# USB-HUB-MUX.net
KiCad netlist of a schematic drawn in Altium Designer
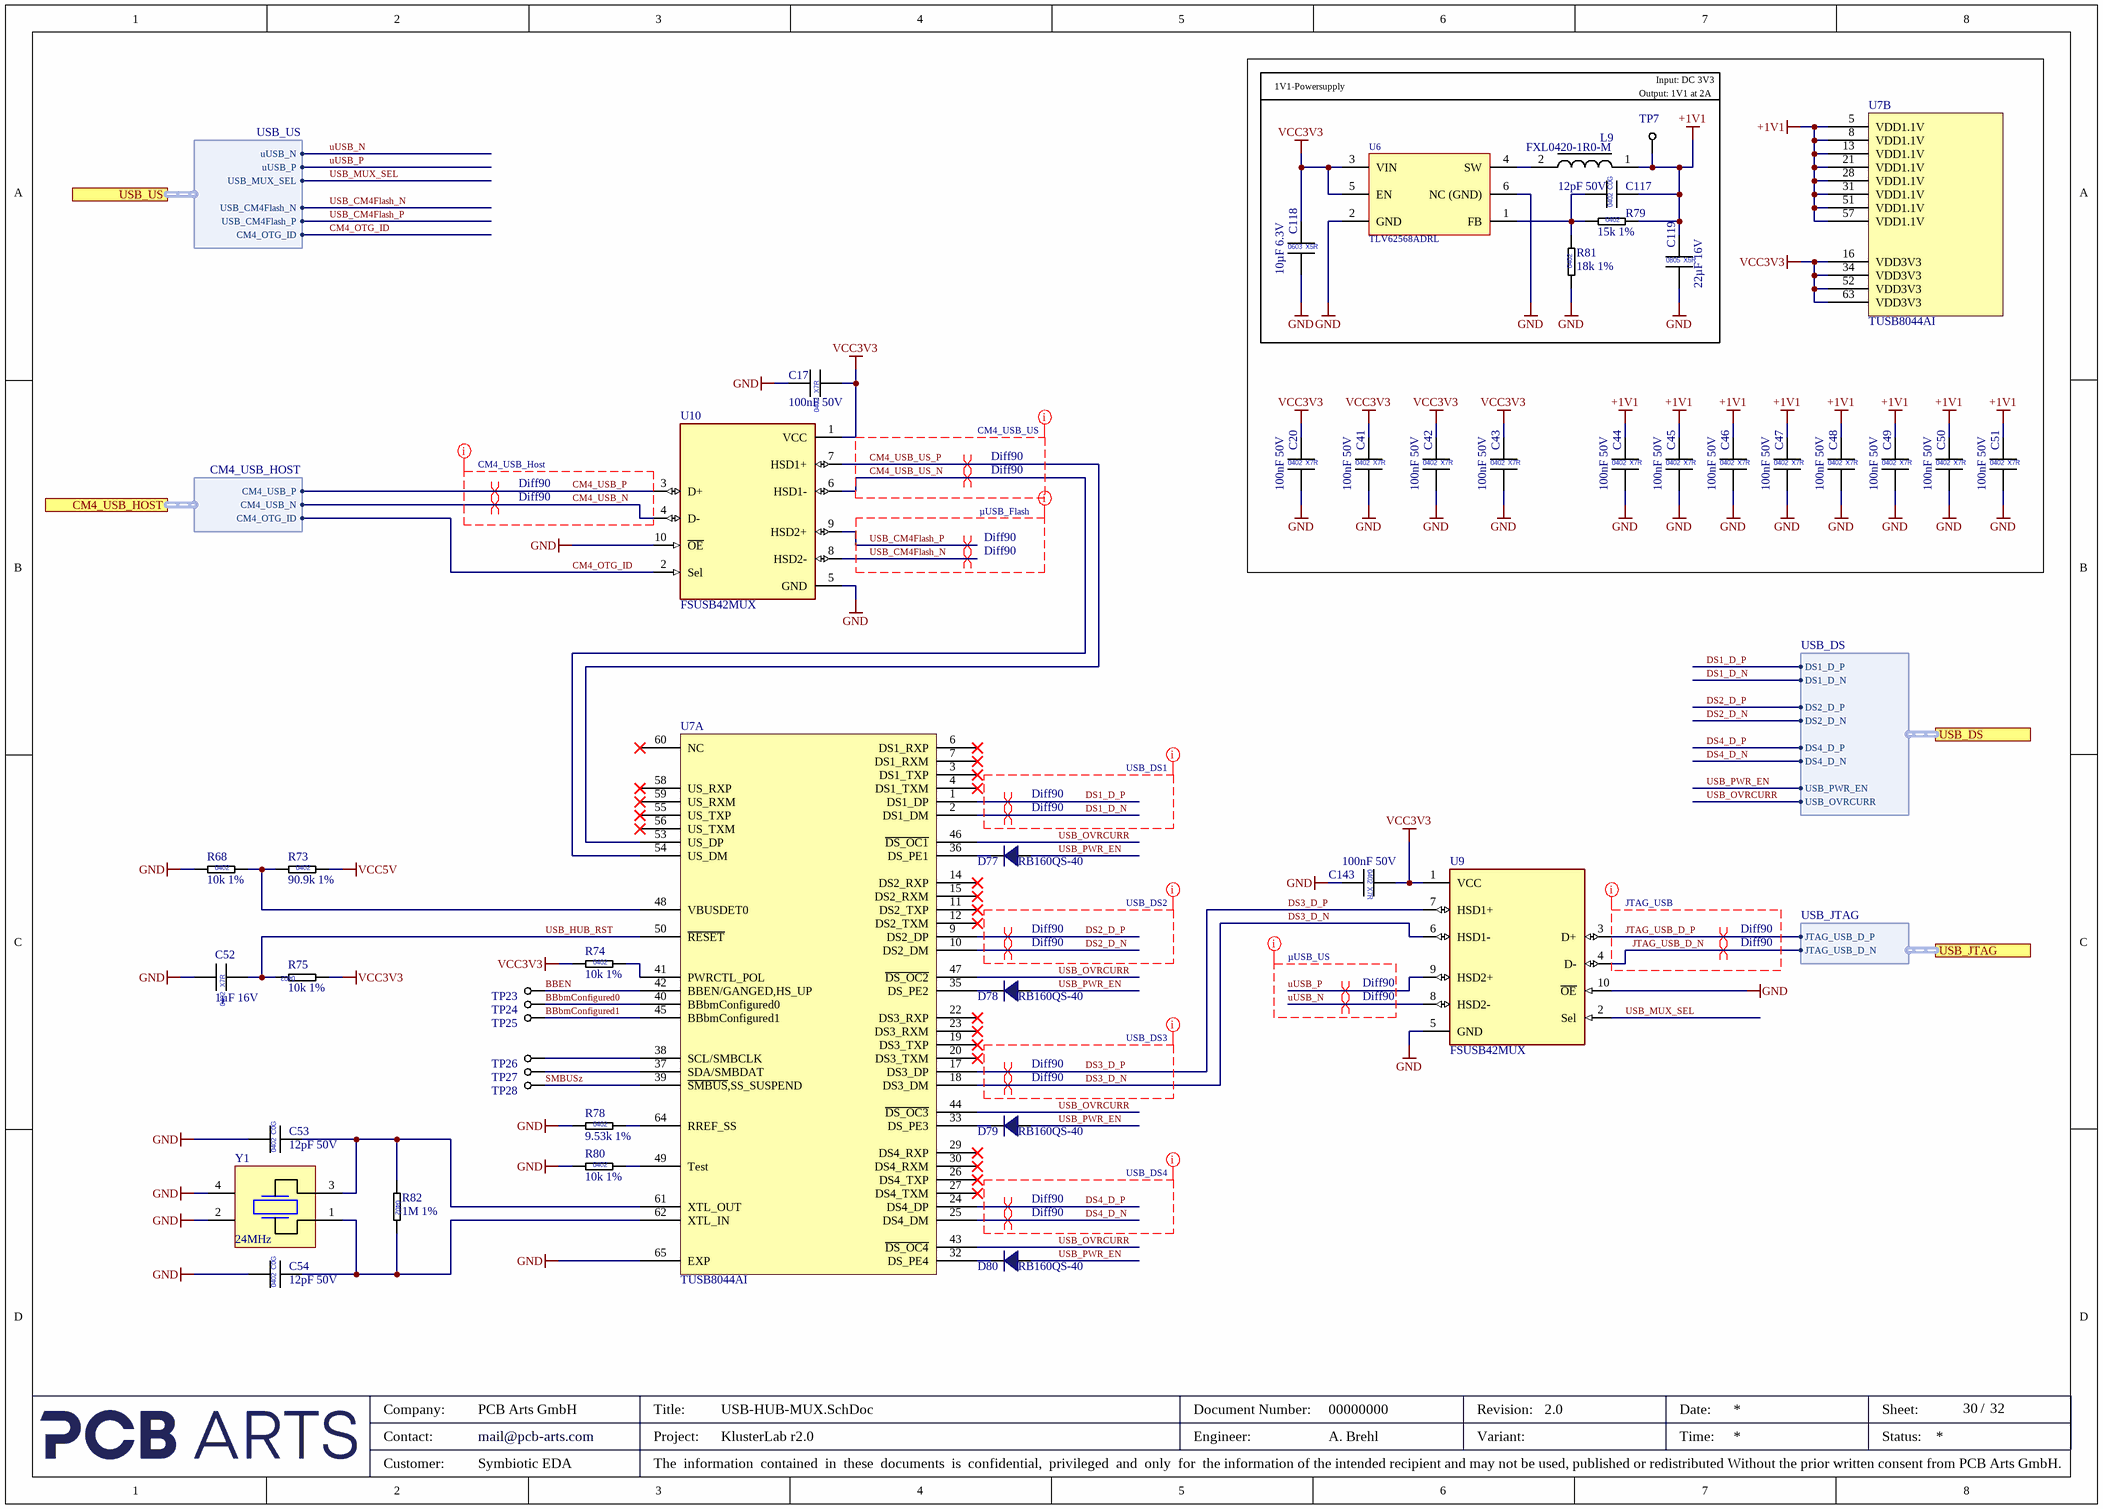
[diagram p0: USB-HUB-MUX.SchDoc]

(export (version "E")
  (design (tool "Eeschema 10.0.6"))
  (components
    (comp (ref "C17")
      (value "100nF 50V")
      (footprint "Cap:CAP_0402_L")
      (description "Multilayer Ceramic Capacitors MLCC - SMD/SMT 0402 50VDC")
      (libsource (lib "Cap") (part "CAP_0402_100nF_50V"))
    )
    (comp (ref "C20")
      (value "100nF 50V")
      (footprint "Cap:CAP_0402_L")
      (description "Multilayer Ceramic Capacitors MLCC - SMD/SMT 0402 50VDC")
      (libsource (lib "Cap") (part "CAP_0402_100nF_50V"))
    )
    (comp (ref "C41")
      (value "100nF 50V")
      (footprint "Cap:CAP_0402_L")
      (description "Multilayer Ceramic Capacitors MLCC - SMD/SMT 0402 50VDC")
      (libsource (lib "Cap") (part "CAP_0402_100nF_50V"))
    )
    (comp (ref "C42")
      (value "100nF 50V")
      (footprint "Cap:CAP_0402_L")
      (description "Multilayer Ceramic Capacitors MLCC - SMD/SMT 0402 50VDC")
      (libsource (lib "Cap") (part "CAP_0402_100nF_50V"))
    )
    (comp (ref "C43")
      (value "100nF 50V")
      (footprint "Cap:CAP_0402_L")
      (description "Multilayer Ceramic Capacitors MLCC - SMD/SMT 0402 50VDC")
      (libsource (lib "Cap") (part "CAP_0402_100nF_50V"))
    )
    (comp (ref "C44")
      (value "100nF 50V")
      (footprint "Cap:CAP_0402_L")
      (description "Multilayer Ceramic Capacitors MLCC - SMD/SMT 0402 50VDC")
      (libsource (lib "Cap") (part "CAP_0402_100nF_50V"))
    )
    (comp (ref "C45")
      (value "100nF 50V")
      (footprint "Cap:CAP_0402_L")
      (description "Multilayer Ceramic Capacitors MLCC - SMD/SMT 0402 50VDC")
      (libsource (lib "Cap") (part "CAP_0402_100nF_50V"))
    )
    (comp (ref "C46")
      (value "100nF 50V")
      (footprint "Cap:CAP_0402_L")
      (description "Multilayer Ceramic Capacitors MLCC - SMD/SMT 0402 50VDC")
      (libsource (lib "Cap") (part "CAP_0402_100nF_50V"))
    )
    (comp (ref "C47")
      (value "100nF 50V")
      (footprint "Cap:CAP_0402_L")
      (description "Multilayer Ceramic Capacitors MLCC - SMD/SMT 0402 50VDC")
      (libsource (lib "Cap") (part "CAP_0402_100nF_50V"))
    )
    (comp (ref "C48")
      (value "100nF 50V")
      (footprint "Cap:CAP_0402_L")
      (description "Multilayer Ceramic Capacitors MLCC - SMD/SMT 0402 50VDC")
      (libsource (lib "Cap") (part "CAP_0402_100nF_50V"))
    )
    (comp (ref "C49")
      (value "100nF 50V")
      (footprint "Cap:CAP_0402_L")
      (description "Multilayer Ceramic Capacitors MLCC - SMD/SMT 0402 50VDC")
      (libsource (lib "Cap") (part "CAP_0402_100nF_50V"))
    )
    (comp (ref "C50")
      (value "100nF 50V")
      (footprint "Cap:CAP_0402_L")
      (description "Multilayer Ceramic Capacitors MLCC - SMD/SMT 0402 50VDC")
      (libsource (lib "Cap") (part "CAP_0402_100nF_50V"))
    )
    (comp (ref "C51")
      (value "100nF 50V")
      (footprint "Cap:CAP_0402_L")
      (description "Multilayer Ceramic Capacitors MLCC - SMD/SMT 0402 50VDC")
      (libsource (lib "Cap") (part "CAP_0402_100nF_50V"))
    )
    (comp (ref "C52")
      (value "1µF 16V")
      (footprint "CAP_0402_L")
      (description "Multilayer Ceramic Capacitors MLCC - SMD/SMT 0402 16VDC")
      (libsource (lib "MIKO 202007") (part "CAP_0402_1µF_16V"))
    )
    (comp (ref "C53")
      (value "12pF 50V")
      (footprint "Cap:CAP_0402_L")
      (description "Multilayer Ceramic Capacitors MLCC - SMD/SMT 0402 50VDC")
      (libsource (lib "Cap") (part "CAP_0402_12pF_50V"))
    )
    (comp (ref "C54")
      (value "12pF 50V")
      (footprint "Cap:CAP_0402_L")
      (description "Multilayer Ceramic Capacitors MLCC - SMD/SMT 0402 50VDC")
      (libsource (lib "Cap") (part "CAP_0402_12pF_50V"))
    )
    (comp (ref "C117")
      (value "12pF 50V")
      (footprint "Cap:CAP_0402_L")
      (description "Multilayer Ceramic Capacitors MLCC - SMD/SMT 0402 50VDC")
      (libsource (lib "Cap") (part "CAP_0402_12pF_50V"))
    )
    (comp (ref "C118")
      (value "10µF 6.3V")
      (footprint "Cap:CAP_0603_L")
      (description "Multilayer Ceramic Capacitors MLCC - SMD/SMT 0603 6.3VDC")
      (libsource (lib "Cap") (part "CAP_0603_10µF_6.3V"))
    )
    (comp (ref "C119")
      (value "22µF 16V")
      (footprint "Cap:CAP_0805")
      (description "Multilayer Ceramic Capacitors MLCC - SMD/SMT 0805 16VDC")
      (libsource (lib "Cap") (part "CAP_0805_22µF_16V"))
    )
    (comp (ref "C143")
      (value "100nF 50V")
      (footprint "Cap:CAP_0402_L")
      (description "Multilayer Ceramic Capacitors MLCC - SMD/SMT 0402 50VDC")
      (libsource (lib "Cap") (part "CAP_0402_100nF_50V"))
    )
    (comp (ref "D77")
      (value "RB160QS-40")
      (footprint "Active:SOD-882")
      (description "Schottky Dioden & Gleichrichter 40V SCHOTTKY DIODES & RECTIFIERS")
      (libsource (lib "Active") (part "RB160QS-40_Schottky Dioden & Gleichrichter 40V"))
    )
    (comp (ref "D78")
      (value "RB160QS-40")
      (footprint "Active:SOD-882")
      (description "Schottky Dioden & Gleichrichter 40V SCHOTTKY DIODES & RECTIFIERS")
      (libsource (lib "Active") (part "RB160QS-40_Schottky Dioden & Gleichrichter 40V"))
    )
    (comp (ref "D79")
      (value "RB160QS-40")
      (footprint "Active:SOD-882")
      (description "Schottky Dioden & Gleichrichter 40V SCHOTTKY DIODES & RECTIFIERS")
      (libsource (lib "Active") (part "RB160QS-40_Schottky Dioden & Gleichrichter 40V"))
    )
    (comp (ref "D80")
      (value "RB160QS-40")
      (footprint "Active:SOD-882")
      (description "Schottky Dioden & Gleichrichter 40V SCHOTTKY DIODES & RECTIFIERS")
      (libsource (lib "Active") (part "RB160QS-40_Schottky Dioden & Gleichrichter 40V"))
    )
    (comp (ref "L9")
      (value "FXL0420-1R0-M")
      (footprint "Indc:FXL0420-1R0-M")
      (description "1uH ±20% 6A 27mΩ SMD,4.4x4.5x1.8mm Power Inductor")
      (libsource (lib "Indc") (part "1uH 6A 27mΩ  FXL0420-1R0-M"))
    )
    (comp (ref "R68")
      (value "10k 1%")
      (footprint "Res:RES_0402_L")
      (description "Thick Film Resistors - SMD 10kOhm 1%")
      (libsource (lib "Res") (part "RES_0402_10k_1%"))
    )
    (comp (ref "R73")
      (value "90.9k 1%")
      (footprint "Res:RES_0402_L")
      (description "Thick Film Resistors - SMD 90.9k 1%")
      (libsource (lib "Res") (part "RES_0402_90.9k_1%"))
    )
    (comp (ref "R74")
      (value "10k 1%")
      (footprint "Res:RES_0402_L")
      (description "Thick Film Resistors - SMD 10kOhm 1%")
      (libsource (lib "Res") (part "RES_0402_10k_1%"))
    )
    (comp (ref "R75")
      (value "10k 1%")
      (footprint "Res:RES_0402_L")
      (description "Thick Film Resistors - SMD 10kOhm 1%")
      (libsource (lib "Res") (part "RES_0402_10k_1%"))
    )
    (comp (ref "R78")
      (value "9.53k 1%")
      (footprint "Res:RES_0402_L")
      (description "Thick Film Resistors - SMD 9.53kOhm 1%")
      (libsource (lib "Res") (part "RES_0402_9.53k_1%"))
    )
    (comp (ref "R79")
      (value "15k 1%")
      (footprint "Res:RES_0402_L")
      (description "Thick Film Resistors - SMD 15kOhm 1%")
      (libsource (lib "Res") (part "RES_0402_15k_1%"))
    )
    (comp (ref "R80")
      (value "10k 1%")
      (footprint "Res:RES_0402_L")
      (description "Thick Film Resistors - SMD 10kOhm 1%")
      (libsource (lib "Res") (part "RES_0402_10k_1%"))
    )
    (comp (ref "R81")
      (value "18k 1%")
      (footprint "Res:RES_0402_L")
      (description "Thick Film Resistors - SMD 18kOhm 1%")
      (libsource (lib "Res") (part "RES_0402_18k_1%"))
    )
    (comp (ref "R82")
      (value "1M 1%")
      (footprint "Res:RES_0402_L")
      (description "Thick Film Resistors - SMD 1MOhm 1%")
      (libsource (lib "Res") (part "RES_0402_1M_1%"))
    )
    (comp (ref "TP7")
      (value "Testpoint")
      (footprint "Electro_mech:Testpoint 0.8mm")
      (description "Testpoint 0.8mm")
      (libsource (lib "Electro_Mech") (part "Testpoint 0.8mm"))
    )
    (comp (ref "TP23")
      (value "Testpoint")
      (footprint "Electro_mech:Testpoint 0.8mm")
      (description "Testpoint 0.8mm")
      (libsource (lib "Electro_Mech") (part "Testpoint 0.8mm"))
    )
    (comp (ref "TP24")
      (value "Testpoint")
      (footprint "Electro_mech:Testpoint 0.8mm")
      (description "Testpoint 0.8mm")
      (libsource (lib "Electro_Mech") (part "Testpoint 0.8mm"))
    )
    (comp (ref "TP25")
      (value "Testpoint")
      (footprint "Electro_mech:Testpoint 0.8mm")
      (description "Testpoint 0.8mm")
      (libsource (lib "Electro_Mech") (part "Testpoint 0.8mm"))
    )
    (comp (ref "TP26")
      (value "Testpoint")
      (footprint "Electro_mech:Testpoint 0.8mm")
      (description "Testpoint 0.8mm")
      (libsource (lib "Electro_Mech") (part "Testpoint 0.8mm"))
    )
    (comp (ref "TP27")
      (value "Testpoint")
      (footprint "Electro_mech:Testpoint 0.8mm")
      (description "Testpoint 0.8mm")
      (libsource (lib "Electro_Mech") (part "Testpoint 0.8mm"))
    )
    (comp (ref "TP28")
      (value "Testpoint")
      (footprint "Electro_mech:Testpoint 0.8mm")
      (description "Testpoint 0.8mm")
      (libsource (lib "Electro_Mech") (part "Testpoint 0.8mm"))
    )
    (comp (ref "U6")
      (value "TLV62568ADRL")
      (footprint "Power:SON50P150X80-6N")
      (description "Step Down Converter with Forced PWM in SOT563 Package")
      (libsource (lib "Power") (part "TLV62568ADRL_Step Down Converter 1A; 2A"))
    )
    (comp (ref "U7")
      (value "TUSB8044AI")
      (footprint "Digital:QFN50P900X900X90_HS-65N")
      (description "USB Hub IC, USB 3.2, 5Gbps, 4 Ports, industrial Temperature")
      (libsource (lib "Digital") (part "TUSB8044AI_USB Hub IC, USB 3.2, 5Gbps, 4 Ports, industrial Temperature"))
    )
    (comp (ref "U9")
      (value "FSUSB42MUX")
      (footprint "digital:SOP50P300X300X110-10N")
      (description "IC USB SWITCH DPDT")
      (libsource (lib "Digital") (part "FSUSB42MUX_IC USB SWITCH DPDT"))
    )
    (comp (ref "U10")
      (value "FSUSB42MUX")
      (footprint "digital:SOP50P300X300X110-10N")
      (description "IC USB SWITCH DPDT")
      (libsource (lib "") (part "FSUSB42MUX_IC USB SWITCH DPDT_1"))
    )
    (comp (ref "Y1")
      (value "ECS-240-10-36B2-CTN-TR")
      (footprint "Timer:ECX-2236B")
      (description "2.5 x 2.0 x 0.55 mm SMD Crystal")
      (fields (field (name "FREQUENCY") "24MHz"))
      (libsource (lib "Timer") (part "Quarz 24MHz ESR 50R10pF"))
    )
  )
  (nets
    (net (code "5") (name "+1V1") (class "Default")
      (node (ref "C117") (pin "2") (pinfunction "2_2") (pintype "passive"))
      (node (ref "C119") (pin "1") (pinfunction "1_1") (pintype "passive"))
      (node (ref "C44") (pin "1") (pinfunction "1_1") (pintype "passive"))
      (node (ref "C45") (pin "1") (pinfunction "1_1") (pintype "passive"))
      (node (ref "C46") (pin "1") (pinfunction "1_1") (pintype "passive"))
      (node (ref "C47") (pin "1") (pinfunction "1_1") (pintype "passive"))
      (node (ref "C48") (pin "1") (pinfunction "1_1") (pintype "passive"))
      (node (ref "C49") (pin "1") (pinfunction "1_1") (pintype "passive"))
      (node (ref "C50") (pin "1") (pinfunction "1_1") (pintype "passive"))
      (node (ref "C51") (pin "1") (pinfunction "1_1") (pintype "passive"))
      (node (ref "L9") (pin "1") (pinfunction "1_1") (pintype "passive"))
      (node (ref "R79") (pin "2") (pinfunction "2_2") (pintype "passive"))
      (node (ref "TP7") (pin "1") (pinfunction "GND_1") (pintype "passive"))
      (node (ref "U7") (pin "13") (pinfunction "VDD1.1V_13") (pintype "passive"))
      (node (ref "U7") (pin "21") (pinfunction "VDD1.1V_21") (pintype "passive"))
      (node (ref "U7") (pin "28") (pinfunction "VDD1.1V_28") (pintype "passive"))
      (node (ref "U7") (pin "31") (pinfunction "VDD1.1V_31") (pintype "passive"))
      (node (ref "U7") (pin "5") (pinfunction "VDD1.1V_5") (pintype "passive"))
      (node (ref "U7") (pin "51") (pinfunction "VDD1.1V_51") (pintype "passive"))
      (node (ref "U7") (pin "57") (pinfunction "VDD1.1V_57") (pintype "passive"))
      (node (ref "U7") (pin "8") (pinfunction "VDD1.1V_8") (pintype "passive"))
    )
    (net (code "6") (name "/BBEN") (class "Default")
      (node (ref "TP23") (pin "1") (pinfunction "GND_1") (pintype "passive"))
      (node (ref "U7") (pin "42") (pinfunction "BBEN/GANGED,HS_UP_42") (pintype "passive"))
    )
    (net (code "7") (name "/BBbmConfigured0") (class "Default")
      (node (ref "TP24") (pin "1") (pinfunction "GND_1") (pintype "passive"))
      (node (ref "U7") (pin "40") (pinfunction "BBbmConfigured0_40") (pintype "passive"))
    )
    (net (code "8") (name "/BBbmConfigured1") (class "Default")
      (node (ref "TP25") (pin "1") (pinfunction "GND_1") (pintype "passive"))
      (node (ref "U7") (pin "45") (pinfunction "BBbmConfigured1_45") (pintype "passive"))
    )
    (net (code "9") (name "/CM4_OTG_ID") (class "Default")
      (node (ref "U10") (pin "2") (pinfunction "Sel_2") (pintype "input"))
    )
    (net (code "10") (name "/CM4_USB_N") (class "Default")
      (node (ref "U10") (pin "4") (pinfunction "D-_4") (pintype "bidirectional"))
    )
    (net (code "11") (name "/CM4_USB_P") (class "Default")
      (node (ref "U10") (pin "3") (pinfunction "D+_3") (pintype "bidirectional"))
    )
    (net (code "12") (name "/CM4_USB_US_N") (class "Default")
      (node (ref "U10") (pin "6") (pinfunction "HSD1-_6") (pintype "bidirectional"))
      (node (ref "U7") (pin "54") (pinfunction "US_DM_54") (pintype "passive"))
    )
    (net (code "13") (name "/CM4_USB_US_P") (class "Default")
      (node (ref "U10") (pin "7") (pinfunction "HSD1+_7") (pintype "bidirectional"))
      (node (ref "U7") (pin "53") (pinfunction "US_DP_53") (pintype "passive"))
    )
    (net (code "14") (name "/DS1_D_N") (class "Default")
      (node (ref "U7") (pin "2") (pinfunction "DS1_DM_2") (pintype "passive"))
    )
    (net (code "15") (name "/DS1_D_P") (class "Default")
      (node (ref "U7") (pin "1") (pinfunction "DS1_DP_1") (pintype "passive"))
    )
    (net (code "16") (name "/DS2_D_N") (class "Default")
      (node (ref "U7") (pin "10") (pinfunction "DS2_DM_10") (pintype "passive"))
    )
    (net (code "17") (name "/DS2_D_P") (class "Default")
      (node (ref "U7") (pin "9") (pinfunction "DS2_DP_9") (pintype "passive"))
    )
    (net (code "18") (name "/DS3_D_N") (class "Default")
      (node (ref "U7") (pin "18") (pinfunction "DS3_DM_18") (pintype "passive"))
      (node (ref "U9") (pin "6") (pinfunction "HSD1-_6") (pintype "bidirectional"))
    )
    (net (code "19") (name "/DS3_D_P") (class "Default")
      (node (ref "U7") (pin "17") (pinfunction "DS3_DP_17") (pintype "passive"))
      (node (ref "U9") (pin "7") (pinfunction "HSD1+_7") (pintype "bidirectional"))
    )
    (net (code "20") (name "/DS4_D_N") (class "Default")
      (node (ref "U7") (pin "25") (pinfunction "DS4_DM_25") (pintype "passive"))
    )
    (net (code "21") (name "/DS4_D_P") (class "Default")
      (node (ref "U7") (pin "24") (pinfunction "DS4_DP_24") (pintype "passive"))
    )
    (net (code "22") (name "/JTAG_USB_D_N") (class "Default")
      (node (ref "U9") (pin "4") (pinfunction "D-_4") (pintype "bidirectional"))
    )
    (net (code "23") (name "/JTAG_USB_D_P") (class "Default")
      (node (ref "U9") (pin "3") (pinfunction "D+_3") (pintype "bidirectional"))
    )
    (net (code "24") (name "/SMBUSz") (class "Default")
      (node (ref "TP28") (pin "1") (pinfunction "GND_1") (pintype "passive"))
      (node (ref "U7") (pin "39") (pinfunction "~{SMBUS},SS_SUSPEND_39") (pintype "passive"))
    )
    (net (code "25") (name "/USB_CM4Flash_N") (class "Default")
      (node (ref "U10") (pin "8") (pinfunction "HSD2-_8") (pintype "bidirectional"))
    )
    (net (code "26") (name "/USB_CM4Flash_P") (class "Default")
      (node (ref "U10") (pin "9") (pinfunction "HSD2+_9") (pintype "bidirectional"))
    )
    (net (code "27") (name "/USB_HUB_RST") (class "Default")
      (node (ref "C52") (pin "1") (pinfunction "1_1") (pintype "passive"))
      (node (ref "R75") (pin "1") (pinfunction "1_1") (pintype "passive"))
      (node (ref "U7") (pin "50") (pinfunction "~{RESET}_50") (pintype "passive"))
    )
    (net (code "28") (name "/USB_MUX_SEL") (class "Default")
      (node (ref "U9") (pin "2") (pinfunction "Sel_2") (pintype "input"))
    )
    (net (code "29") (name "/USB_OVRCURR") (class "Default")
      (node (ref "U7") (pin "43") (pinfunction "~{DS_OC4}_43") (pintype "passive"))
      (node (ref "U7") (pin "44") (pinfunction "~{DS_OC3}_44") (pintype "passive"))
      (node (ref "U7") (pin "46") (pinfunction "~{DS_OC1}_46") (pintype "passive"))
      (node (ref "U7") (pin "47") (pinfunction "~{DS_OC2}_47") (pintype "passive"))
    )
    (net (code "30") (name "/USB_PWR_EN") (class "Default")
      (node (ref "D77") (pin "2") (pinfunction "2_2") (pintype "passive"))
      (node (ref "D78") (pin "2") (pinfunction "2_2") (pintype "passive"))
      (node (ref "D79") (pin "2") (pinfunction "2_2") (pintype "passive"))
      (node (ref "D80") (pin "2") (pinfunction "2_2") (pintype "passive"))
    )
    (net (code "31") (name "/uUSB_N") (class "Default")
      (node (ref "U9") (pin "8") (pinfunction "HSD2-_8") (pintype "bidirectional"))
    )
    (net (code "32") (name "/uUSB_P") (class "Default")
      (node (ref "U9") (pin "9") (pinfunction "HSD2+_9") (pintype "bidirectional"))
    )
    (net (code "37") (name "GND") (class "Default")
      (node (ref "C118") (pin "2") (pinfunction "2_2") (pintype "passive"))
      (node (ref "C119") (pin "2") (pinfunction "2_2") (pintype "passive"))
      (node (ref "C143") (pin "2") (pinfunction "2_2") (pintype "passive"))
      (node (ref "C17") (pin "2") (pinfunction "2_2") (pintype "passive"))
      (node (ref "C20") (pin "2") (pinfunction "2_2") (pintype "passive"))
      (node (ref "C41") (pin "2") (pinfunction "2_2") (pintype "passive"))
      (node (ref "C42") (pin "2") (pinfunction "2_2") (pintype "passive"))
      (node (ref "C43") (pin "2") (pinfunction "2_2") (pintype "passive"))
      (node (ref "C44") (pin "2") (pinfunction "2_2") (pintype "passive"))
      (node (ref "C45") (pin "2") (pinfunction "2_2") (pintype "passive"))
      (node (ref "C46") (pin "2") (pinfunction "2_2") (pintype "passive"))
      (node (ref "C47") (pin "2") (pinfunction "2_2") (pintype "passive"))
      (node (ref "C48") (pin "2") (pinfunction "2_2") (pintype "passive"))
      (node (ref "C49") (pin "2") (pinfunction "2_2") (pintype "passive"))
      (node (ref "C50") (pin "2") (pinfunction "2_2") (pintype "passive"))
      (node (ref "C51") (pin "2") (pinfunction "2_2") (pintype "passive"))
      (node (ref "C52") (pin "2") (pinfunction "2_2") (pintype "passive"))
      (node (ref "C53") (pin "1") (pinfunction "1_1") (pintype "passive"))
      (node (ref "C54") (pin "1") (pinfunction "1_1") (pintype "passive"))
      (node (ref "R68") (pin "1") (pinfunction "1_1") (pintype "passive"))
      (node (ref "R78") (pin "1") (pinfunction "1_1") (pintype "passive"))
      (node (ref "R80") (pin "1") (pinfunction "1_1") (pintype "passive"))
      (node (ref "R81") (pin "1") (pinfunction "1_1") (pintype "passive"))
      (node (ref "U10") (pin "10") (pinfunction "~{OE}_10") (pintype "input"))
      (node (ref "U10") (pin "5") (pinfunction "GND_5") (pintype "power_in"))
      (node (ref "U6") (pin "2") (pinfunction "GND_2") (pintype "passive"))
      (node (ref "U6") (pin "6") (pinfunction "NC_(GND)_6") (pintype "passive"))
      (node (ref "U7") (pin "65") (pinfunction "EXP_65") (pintype "passive"))
      (node (ref "U9") (pin "10") (pinfunction "~{OE}_10") (pintype "input"))
      (node (ref "U9") (pin "5") (pinfunction "GND_5") (pintype "power_in"))
      (node (ref "Y1") (pin "2") (pinfunction "2_2") (pintype "passive"))
      (node (ref "Y1") (pin "4") (pinfunction "4_4") (pintype "passive"))
    )
    (net (code "38") (name "Net-(TP26-GND)") (class "Default")
      (node (ref "TP26") (pin "1") (pinfunction "GND_1") (pintype "passive"))
      (node (ref "U7") (pin "38") (pinfunction "SCL/SMBCLK_38") (pintype "passive"))
    )
    (net (code "39") (name "Net-(TP27-GND)") (class "Default")
      (node (ref "TP27") (pin "1") (pinfunction "GND_1") (pintype "passive"))
      (node (ref "U7") (pin "37") (pinfunction "SDA/SMBDAT_37") (pintype "passive"))
    )
    (net (code "40") (name "Net-(U6-FB)") (class "Default")
      (node (ref "C117") (pin "1") (pinfunction "1_1") (pintype "passive"))
      (node (ref "R79") (pin "1") (pinfunction "1_1") (pintype "passive"))
      (node (ref "R81") (pin "2") (pinfunction "2_2") (pintype "passive"))
      (node (ref "U6") (pin "1") (pinfunction "FB_1") (pintype "passive"))
    )
    (net (code "41") (name "Net-(U6-SW)") (class "Default")
      (node (ref "L9") (pin "2") (pinfunction "2_2") (pintype "passive"))
      (node (ref "U6") (pin "4") (pinfunction "SW_4") (pintype "passive"))
    )
    (net (code "42") (name "Net-(U7A-DS_PE1)") (class "Default")
      (node (ref "D77") (pin "1") (pinfunction "1_1") (pintype "passive"))
      (node (ref "U7") (pin "36") (pinfunction "DS_PE1_36") (pintype "passive"))
    )
    (net (code "43") (name "Net-(U7A-DS_PE2)") (class "Default")
      (node (ref "D78") (pin "1") (pinfunction "1_1") (pintype "passive"))
      (node (ref "U7") (pin "35") (pinfunction "DS_PE2_35") (pintype "passive"))
    )
    (net (code "44") (name "Net-(U7A-DS_PE3)") (class "Default")
      (node (ref "D79") (pin "1") (pinfunction "1_1") (pintype "passive"))
      (node (ref "U7") (pin "33") (pinfunction "DS_PE3_33") (pintype "passive"))
    )
    (net (code "45") (name "Net-(U7A-DS_PE4)") (class "Default")
      (node (ref "D80") (pin "1") (pinfunction "1_1") (pintype "passive"))
      (node (ref "U7") (pin "32") (pinfunction "DS_PE4_32") (pintype "passive"))
    )
    (net (code "46") (name "Net-(U7A-PWRCTL_POL)") (class "Default")
      (node (ref "R74") (pin "2") (pinfunction "2_2") (pintype "passive"))
      (node (ref "U7") (pin "41") (pinfunction "PWRCTL_POL_41") (pintype "passive"))
    )
    (net (code "47") (name "Net-(U7A-RREF_SS)") (class "Default")
      (node (ref "R78") (pin "2") (pinfunction "2_2") (pintype "passive"))
      (node (ref "U7") (pin "64") (pinfunction "RREF_SS_64") (pintype "passive"))
    )
    (net (code "48") (name "Net-(U7A-Test)") (class "Default")
      (node (ref "R80") (pin "2") (pinfunction "2_2") (pintype "passive"))
      (node (ref "U7") (pin "49") (pinfunction "Test_49") (pintype "passive"))
    )
    (net (code "49") (name "Net-(U7A-VBUSDET0)") (class "Default")
      (node (ref "R68") (pin "2") (pinfunction "2_2") (pintype "passive"))
      (node (ref "R73") (pin "1") (pinfunction "1_1") (pintype "passive"))
      (node (ref "U7") (pin "48") (pinfunction "VBUSDET0_48") (pintype "passive"))
    )
    (net (code "50") (name "Net-(U7A-XTL_IN)") (class "Default")
      (node (ref "C54") (pin "2") (pinfunction "2_2") (pintype "passive"))
      (node (ref "R82") (pin "2") (pinfunction "2_2") (pintype "passive"))
      (node (ref "U7") (pin "62") (pinfunction "XTL_IN_62") (pintype "passive"))
      (node (ref "Y1") (pin "1") (pinfunction "1_1") (pintype "passive"))
    )
    (net (code "51") (name "Net-(U7A-XTL_OUT)") (class "Default")
      (node (ref "C53") (pin "2") (pinfunction "2_2") (pintype "passive"))
      (node (ref "R82") (pin "1") (pinfunction "1_1") (pintype "passive"))
      (node (ref "U7") (pin "61") (pinfunction "XTL_OUT_61") (pintype "passive"))
      (node (ref "Y1") (pin "3") (pinfunction "3_3") (pintype "passive"))
    )
    (net (code "52") (name "VCC3V3") (class "Default")
      (node (ref "C118") (pin "1") (pinfunction "1_1") (pintype "passive"))
      (node (ref "C143") (pin "1") (pinfunction "1_1") (pintype "passive"))
      (node (ref "C17") (pin "1") (pinfunction "1_1") (pintype "passive"))
      (node (ref "C20") (pin "1") (pinfunction "1_1") (pintype "passive"))
      (node (ref "C41") (pin "1") (pinfunction "1_1") (pintype "passive"))
      (node (ref "C42") (pin "1") (pinfunction "1_1") (pintype "passive"))
      (node (ref "C43") (pin "1") (pinfunction "1_1") (pintype "passive"))
      (node (ref "R74") (pin "1") (pinfunction "1_1") (pintype "passive"))
      (node (ref "R75") (pin "2") (pinfunction "2_2") (pintype "passive"))
      (node (ref "U10") (pin "1") (pinfunction "VCC_1") (pintype "power_in"))
      (node (ref "U6") (pin "3") (pinfunction "VIN_3") (pintype "passive"))
      (node (ref "U6") (pin "5") (pinfunction "EN_5") (pintype "passive"))
      (node (ref "U7") (pin "16") (pinfunction "VDD3V3_16") (pintype "passive"))
      (node (ref "U7") (pin "34") (pinfunction "VDD3V3_34") (pintype "passive"))
      (node (ref "U7") (pin "52") (pinfunction "VDD3V3_52") (pintype "passive"))
      (node (ref "U7") (pin "63") (pinfunction "VDD3V3_63") (pintype "passive"))
      (node (ref "U9") (pin "1") (pinfunction "VCC_1") (pintype "power_in"))
    )
    (net (code "53") (name "VCC5V") (class "Default")
      (node (ref "R73") (pin "2") (pinfunction "2_2") (pintype "passive"))
    )
    (net (code "54") (name "unconnected-(U7A-DS1_RXM-Pad7)") (class "Default")
      (node (ref "U7") (pin "7") (pinfunction "DS1_RXM_7") (pintype "passive+no_connect"))
    )
    (net (code "55") (name "unconnected-(U7A-DS1_RXP-Pad6)") (class "Default")
      (node (ref "U7") (pin "6") (pinfunction "DS1_RXP_6") (pintype "passive+no_connect"))
    )
    (net (code "56") (name "unconnected-(U7A-DS1_TXM-Pad4)") (class "Default")
      (node (ref "U7") (pin "4") (pinfunction "DS1_TXM_4") (pintype "passive+no_connect"))
    )
    (net (code "57") (name "unconnected-(U7A-DS1_TXP-Pad3)") (class "Default")
      (node (ref "U7") (pin "3") (pinfunction "DS1_TXP_3") (pintype "passive+no_connect"))
    )
    (net (code "58") (name "unconnected-(U7A-DS2_RXM-Pad15)") (class "Default")
      (node (ref "U7") (pin "15") (pinfunction "DS2_RXM_15") (pintype "passive+no_connect"))
    )
    (net (code "59") (name "unconnected-(U7A-DS2_RXP-Pad14)") (class "Default")
      (node (ref "U7") (pin "14") (pinfunction "DS2_RXP_14") (pintype "passive+no_connect"))
    )
    (net (code "60") (name "unconnected-(U7A-DS2_TXM-Pad12)") (class "Default")
      (node (ref "U7") (pin "12") (pinfunction "DS2_TXM_12") (pintype "passive+no_connect"))
    )
    (net (code "61") (name "unconnected-(U7A-DS2_TXP-Pad11)") (class "Default")
      (node (ref "U7") (pin "11") (pinfunction "DS2_TXP_11") (pintype "passive+no_connect"))
    )
    (net (code "62") (name "unconnected-(U7A-DS3_RXM-Pad23)") (class "Default")
      (node (ref "U7") (pin "23") (pinfunction "DS3_RXM_23") (pintype "passive+no_connect"))
    )
    (net (code "63") (name "unconnected-(U7A-DS3_RXP-Pad22)") (class "Default")
      (node (ref "U7") (pin "22") (pinfunction "DS3_RXP_22") (pintype "passive+no_connect"))
    )
    (net (code "64") (name "unconnected-(U7A-DS3_TXM-Pad20)") (class "Default")
      (node (ref "U7") (pin "20") (pinfunction "DS3_TXM_20") (pintype "passive+no_connect"))
    )
    (net (code "65") (name "unconnected-(U7A-DS3_TXP-Pad19)") (class "Default")
      (node (ref "U7") (pin "19") (pinfunction "DS3_TXP_19") (pintype "passive+no_connect"))
    )
    (net (code "66") (name "unconnected-(U7A-DS4_RXM-Pad30)") (class "Default")
      (node (ref "U7") (pin "30") (pinfunction "DS4_RXM_30") (pintype "passive+no_connect"))
    )
    (net (code "67") (name "unconnected-(U7A-DS4_RXP-Pad29)") (class "Default")
      (node (ref "U7") (pin "29") (pinfunction "DS4_RXP_29") (pintype "passive+no_connect"))
    )
    (net (code "68") (name "unconnected-(U7A-DS4_TXM-Pad27)") (class "Default")
      (node (ref "U7") (pin "27") (pinfunction "DS4_TXM_27") (pintype "passive+no_connect"))
    )
    (net (code "69") (name "unconnected-(U7A-DS4_TXP-Pad26)") (class "Default")
      (node (ref "U7") (pin "26") (pinfunction "DS4_TXP_26") (pintype "passive+no_connect"))
    )
    (net (code "70") (name "unconnected-(U7A-NC-Pad60)") (class "Default")
      (node (ref "U7") (pin "60") (pinfunction "NC_60") (pintype "passive+no_connect"))
    )
    (net (code "71") (name "unconnected-(U7A-US_RXM-Pad59)") (class "Default")
      (node (ref "U7") (pin "59") (pinfunction "US_RXM_59") (pintype "passive+no_connect"))
    )
    (net (code "72") (name "unconnected-(U7A-US_RXP-Pad58)") (class "Default")
      (node (ref "U7") (pin "58") (pinfunction "US_RXP_58") (pintype "passive+no_connect"))
    )
    (net (code "73") (name "unconnected-(U7A-US_TXM-Pad56)") (class "Default")
      (node (ref "U7") (pin "56") (pinfunction "US_TXM_56") (pintype "passive+no_connect"))
    )
    (net (code "74") (name "unconnected-(U7A-US_TXP-Pad55)") (class "Default")
      (node (ref "U7") (pin "55") (pinfunction "US_TXP_55") (pintype "passive+no_connect"))
    )
  )
)
